# Cargador_RasPi3HAT_CamSlot_v1_1.net
KiCad netlist of a schematic drawn in EAGLE
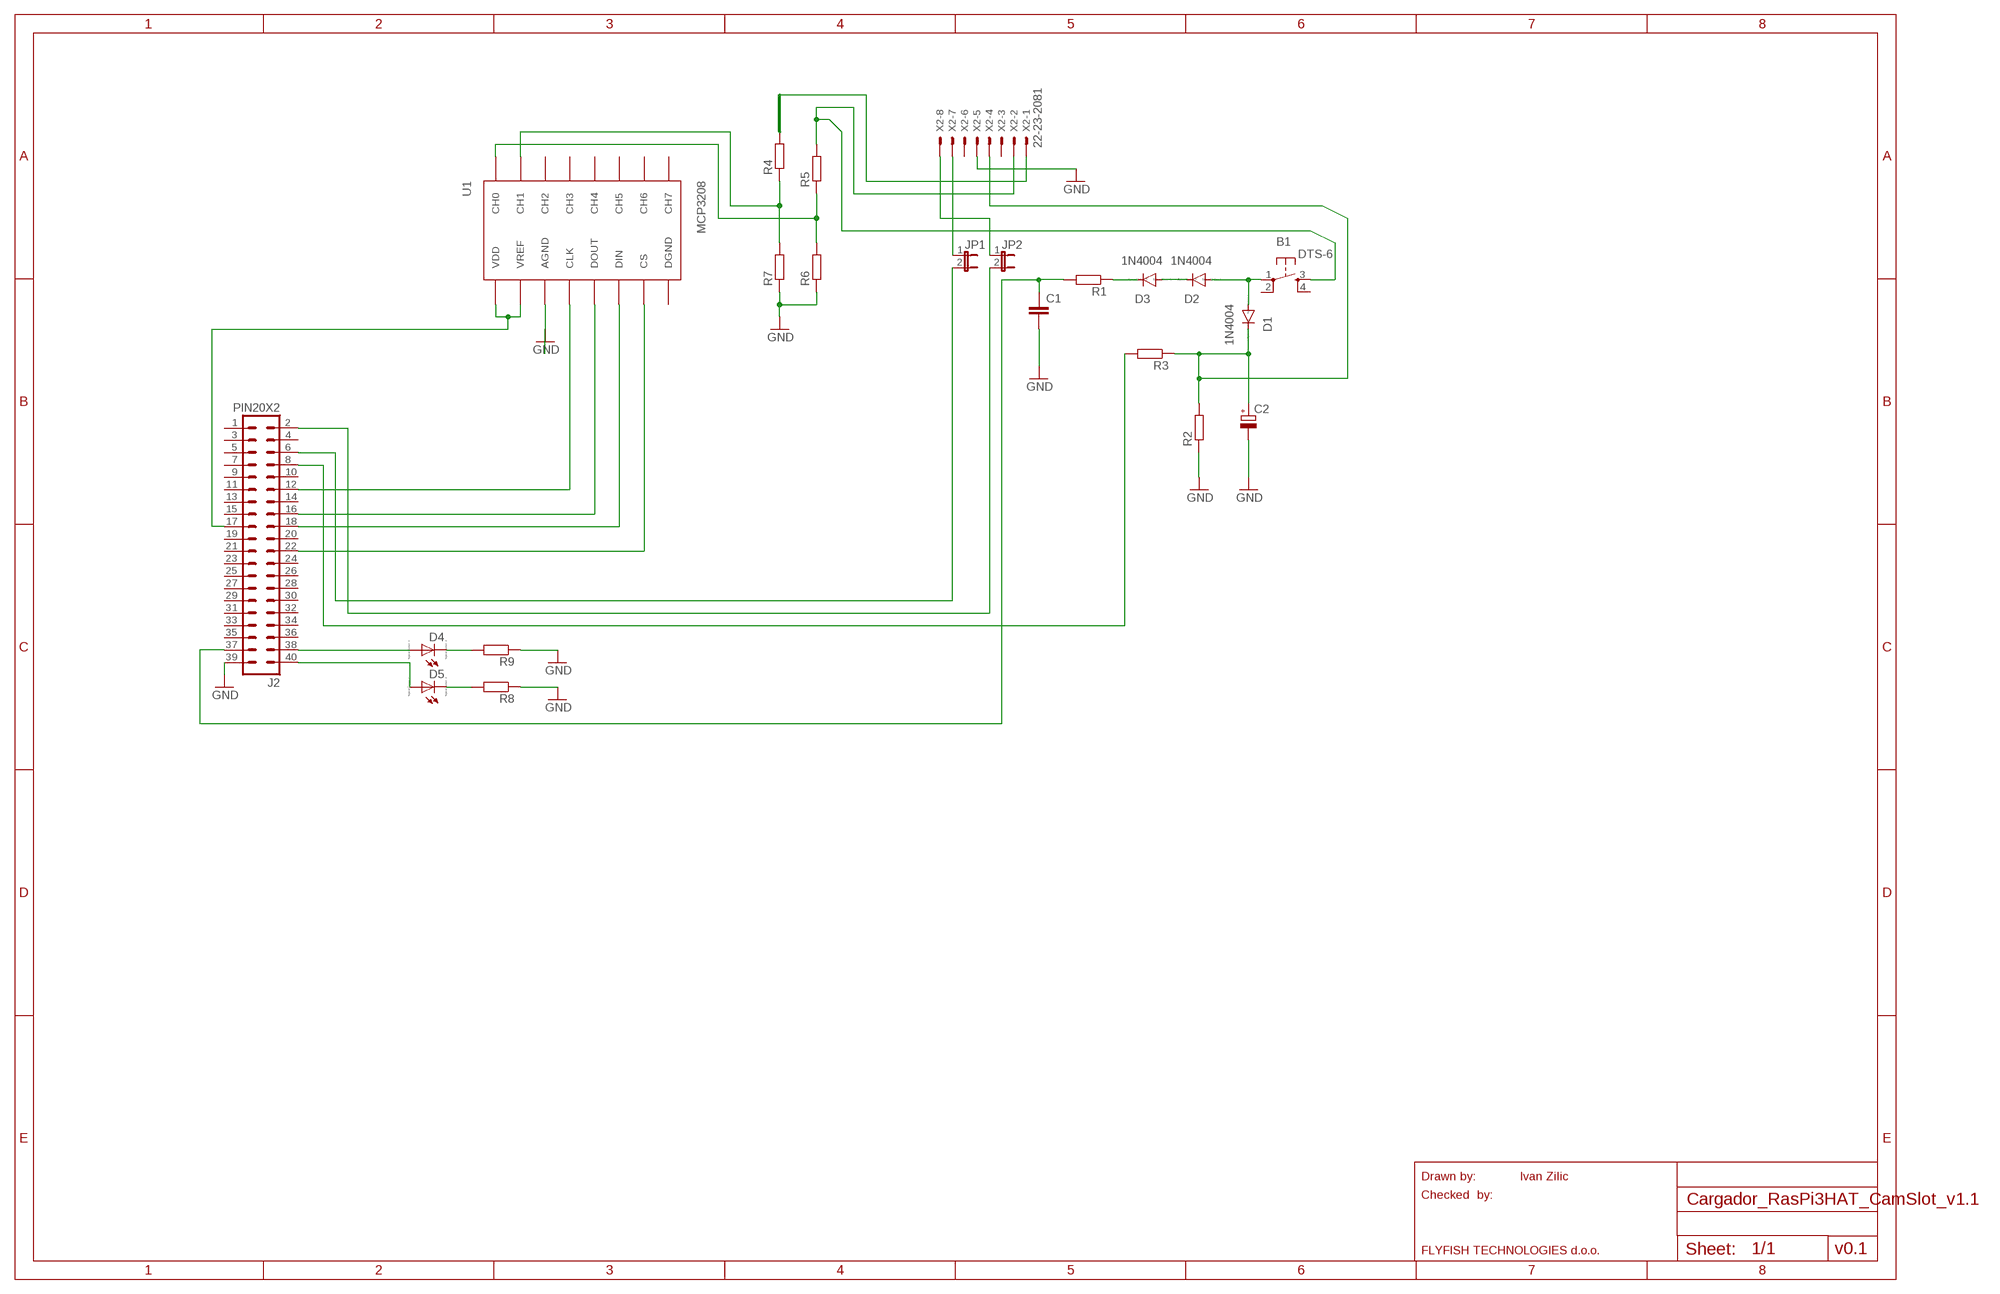
[diagram p0: schematic, sheet 1]

(export (version "E")
  (design (tool "Eeschema 10.0.6"))
  (components
    (comp (ref "B1")
      (value "DTS-6")
      (footprint "eagle-import:DTS-6")
      (libsource (lib "eagle-import") (part "DTS-6"))
    )
    (comp (ref "C1")
      (value "C2.5/2")
      (footprint "eagle-import:C2.5-2")
      (libsource (lib "eagle-import") (part "C2.5/2"))
    )
    (comp (ref "C2")
      (value "CPOL-EUE5-4")
      (footprint "eagle-import:E5-4")
      (libsource (lib "eagle-import") (part "CPOL-EUE5-4"))
    )
    (comp (ref "D1")
      (value "1N4004")
      (footprint "eagle-import:DO41-10")
      (libsource (lib "eagle-import") (part "1N4004"))
    )
    (comp (ref "D2")
      (value "1N4004")
      (footprint "eagle-import:DO41-10")
      (libsource (lib "eagle-import") (part "1N4004"))
    )
    (comp (ref "D3")
      (value "1N4004")
      (footprint "eagle-import:DO41-10")
      (libsource (lib "eagle-import") (part "1N4004"))
    )
    (comp (ref "D4")
      (value "LED_ELD260")
      (footprint "eagle-import:LED_LD260")
      (libsource (lib "eagle-import") (part "LED_ELD260"))
    )
    (comp (ref "D5")
      (value "LED_ELD260")
      (footprint "eagle-import:LED_LD260")
      (libsource (lib "eagle-import") (part "LED_ELD260"))
    )
    (comp (ref "J2")
      (value "PIN20X2")
      (footprint "eagle-import:PIN_20X2")
      (libsource (lib "eagle-import") (part "PIN20X2"))
    )
    (comp (ref "JP1")
      (value "JP1E")
      (footprint "eagle-import:JP1")
      (libsource (lib "eagle-import") (part "JP1E"))
    )
    (comp (ref "JP2")
      (value "JP1E")
      (footprint "eagle-import:JP1")
      (libsource (lib "eagle-import") (part "JP1E"))
    )
    (comp (ref "R1")
      (value "R-EU_0207/10")
      (footprint "eagle-import:0207_10")
      (libsource (lib "eagle-import") (part "R-EU_0207/10"))
    )
    (comp (ref "R2")
      (value "R-EU_0207/10")
      (footprint "eagle-import:0207_10")
      (libsource (lib "eagle-import") (part "R-EU_0207/10"))
    )
    (comp (ref "R3")
      (value "R-EU_0207/10")
      (footprint "eagle-import:0207_10")
      (libsource (lib "eagle-import") (part "R-EU_0207/10"))
    )
    (comp (ref "R4")
      (value "R-EU_0207/10")
      (footprint "eagle-import:0207_10")
      (libsource (lib "eagle-import") (part "R-EU_0207/10"))
    )
    (comp (ref "R5")
      (value "R-EU_0207/10")
      (footprint "eagle-import:0207_10")
      (libsource (lib "eagle-import") (part "R-EU_0207/10"))
    )
    (comp (ref "R6")
      (value "R-EU_0207/10")
      (footprint "eagle-import:0207_10")
      (libsource (lib "eagle-import") (part "R-EU_0207/10"))
    )
    (comp (ref "R7")
      (value "R-EU_0207/10")
      (footprint "eagle-import:0207_10")
      (libsource (lib "eagle-import") (part "R-EU_0207/10"))
    )
    (comp (ref "R8")
      (value "R-EU_0207/10")
      (footprint "eagle-import:0207_10")
      (libsource (lib "eagle-import") (part "R-EU_0207/10"))
    )
    (comp (ref "R9")
      (value "R-EU_0207/10")
      (footprint "eagle-import:0207_10")
      (libsource (lib "eagle-import") (part "R-EU_0207/10"))
    )
    (comp (ref "U1")
      (value "MCP3208")
      (footprint "eagle-import:DIL16")
      (libsource (lib "eagle-import") (part "MCP3208"))
    )
    (comp (ref "X2")
      (value "22-23-2081")
      (footprint "eagle-import:22-23-2081")
      (fields (field (name "MF") "MOLEX"))
      (libsource (lib "eagle-import") (part "22-23-2081"))
    )
  )
  (nets
    (net (code "1") (name "/DGND") (class "Default")
      (node (ref "U1") (pin "DGND") (pinfunction "DGND_DGND") (pintype "power_in"))
    )
    (net (code "2") (name "GND") (class "Default")
      (node (ref "C1") (pin "2") (pinfunction "2_2") (pintype "passive"))
      (node (ref "C2") (pin "-") (pinfunction "-_-") (pintype "passive"))
      (node (ref "J2") (pin "39") (pinfunction "39_39") (pintype "passive"))
      (node (ref "R2") (pin "1") (pinfunction "1_1") (pintype "passive"))
      (node (ref "R6") (pin "1") (pinfunction "1_1") (pintype "passive"))
      (node (ref "R7") (pin "1") (pinfunction "1_1") (pintype "passive"))
      (node (ref "R8") (pin "1") (pinfunction "1_1") (pintype "passive"))
      (node (ref "R9") (pin "1") (pinfunction "1_1") (pintype "passive"))
      (node (ref "U1") (pin "AGND") (pinfunction "AGND_AGND") (pintype "power_in"))
      (node (ref "X2") (pin "5") (pinfunction "S_5") (pintype "passive"))
    )
    (net (code "3") (name "Net-(B1-Pad1)") (class "Default")
      (node (ref "B1") (pin "1") (pinfunction "1_1") (pintype "passive"))
      (node (ref "D1") (pin "A") (pinfunction "A_A") (pintype "passive"))
      (node (ref "D2") (pin "A") (pinfunction "A_A") (pintype "passive"))
    )
    (net (code "4") (name "Net-(C1-Pad1)") (class "Default")
      (node (ref "C1") (pin "1") (pinfunction "1_1") (pintype "passive"))
      (node (ref "J2") (pin "37") (pinfunction "37_37") (pintype "passive"))
      (node (ref "R1") (pin "2") (pinfunction "2_2") (pintype "passive"))
    )
    (net (code "5") (name "Net-(D2-PadC)") (class "Default")
      (node (ref "D2") (pin "C") (pinfunction "C_C") (pintype "passive"))
      (node (ref "D3") (pin "A") (pinfunction "A_A") (pintype "passive"))
    )
    (net (code "6") (name "Net-(D3-PadC)") (class "Default")
      (node (ref "D3") (pin "C") (pinfunction "C_C") (pintype "passive"))
      (node (ref "R1") (pin "1") (pinfunction "1_1") (pintype "passive"))
    )
    (net (code "7") (name "Net-(D4-C)") (class "Default")
      (node (ref "D4") (pin "K") (pinfunction "C_K") (pintype "passive"))
      (node (ref "R9") (pin "2") (pinfunction "2_2") (pintype "passive"))
    )
    (net (code "8") (name "Net-(D4-PadA)") (class "Default")
      (node (ref "D4") (pin "A") (pinfunction "A_A") (pintype "passive"))
      (node (ref "J2") (pin "38") (pinfunction "38_38") (pintype "passive"))
    )
    (net (code "9") (name "Net-(D5-C)") (class "Default")
      (node (ref "D5") (pin "K") (pinfunction "C_K") (pintype "passive"))
      (node (ref "R8") (pin "2") (pinfunction "2_2") (pintype "passive"))
    )
    (net (code "10") (name "Net-(D5-PadA)") (class "Default")
      (node (ref "D5") (pin "A") (pinfunction "A_A") (pintype "passive"))
      (node (ref "J2") (pin "40") (pinfunction "40_40") (pintype "passive"))
    )
    (net (code "11") (name "Net-(J2-Pad2)") (class "Default")
      (node (ref "J2") (pin "2") (pinfunction "2_2") (pintype "passive"))
      (node (ref "JP2") (pin "2") (pinfunction "2_2") (pintype "passive"))
    )
    (net (code "12") (name "Net-(J2-Pad6)") (class "Default")
      (node (ref "J2") (pin "6") (pinfunction "6_6") (pintype "passive"))
      (node (ref "JP1") (pin "2") (pinfunction "2_2") (pintype "passive"))
    )
    (net (code "13") (name "Net-(J2-Pad8)") (class "Default")
      (node (ref "J2") (pin "8") (pinfunction "8_8") (pintype "passive"))
      (node (ref "R3") (pin "2") (pinfunction "2_2") (pintype "passive"))
    )
    (net (code "14") (name "Net-(J2-Pad12)") (class "Default")
      (node (ref "J2") (pin "12") (pinfunction "12_12") (pintype "passive"))
      (node (ref "U1") (pin "CLK") (pinfunction "CLK_CLK") (pintype "input"))
    )
    (net (code "15") (name "Net-(J2-Pad16)") (class "Default")
      (node (ref "J2") (pin "16") (pinfunction "16_16") (pintype "passive"))
      (node (ref "U1") (pin "DOUT") (pinfunction "DOUT_DOUT") (pintype "output"))
    )
    (net (code "16") (name "Net-(J2-Pad17)") (class "Default")
      (node (ref "J2") (pin "17") (pinfunction "17_17") (pintype "passive"))
      (node (ref "U1") (pin "VDD") (pinfunction "VDD_VDD") (pintype "power_in"))
      (node (ref "U1") (pin "VREF") (pinfunction "VREF_VREF") (pintype "input"))
    )
    (net (code "17") (name "Net-(J2-Pad18)") (class "Default")
      (node (ref "J2") (pin "18") (pinfunction "18_18") (pintype "passive"))
      (node (ref "U1") (pin "DIN") (pinfunction "DIN_DIN") (pintype "input"))
    )
    (net (code "18") (name "Net-(J2-Pad22)") (class "Default")
      (node (ref "J2") (pin "22") (pinfunction "22_22") (pintype "passive"))
      (node (ref "U1") (pin "CS") (pinfunction "CS_CS") (pintype "input"))
    )
    (net (code "19") (name "Net-(R4-Pad1)") (class "Default")
      (node (ref "R4") (pin "1") (pinfunction "1_1") (pintype "passive"))
      (node (ref "R7") (pin "2") (pinfunction "2_2") (pintype "passive"))
      (node (ref "U1") (pin "CH1") (pinfunction "CH1_CH1") (pintype "input"))
    )
    (net (code "20") (name "Net-(R5-Pad1)") (class "Default")
      (node (ref "R5") (pin "1") (pinfunction "1_1") (pintype "passive"))
      (node (ref "R6") (pin "2") (pinfunction "2_2") (pintype "passive"))
      (node (ref "U1") (pin "CH0") (pinfunction "CH0_CH0") (pintype "input"))
    )
    (net (code "21") (name "Net-(X2A-S)") (class "Default")
      (node (ref "R4") (pin "2") (pinfunction "2_2") (pintype "passive"))
      (node (ref "X2") (pin "1") (pinfunction "S_1") (pintype "passive"))
    )
    (net (code "22") (name "Net-(X2B-S)") (class "Default")
      (node (ref "B1") (pin "3") (pinfunction "3_3") (pintype "passive"))
      (node (ref "R5") (pin "2") (pinfunction "2_2") (pintype "passive"))
      (node (ref "X2") (pin "2") (pinfunction "S_2") (pintype "passive"))
    )
    (net (code "23") (name "Net-(X2D-S)") (class "Default")
      (node (ref "C2") (pin "+") (pinfunction "+_+") (pintype "passive"))
      (node (ref "D1") (pin "C") (pinfunction "C_C") (pintype "passive"))
      (node (ref "R2") (pin "2") (pinfunction "2_2") (pintype "passive"))
      (node (ref "R3") (pin "1") (pinfunction "1_1") (pintype "passive"))
      (node (ref "X2") (pin "4") (pinfunction "S_4") (pintype "passive"))
    )
    (net (code "24") (name "Net-(X2G-S)") (class "Default")
      (node (ref "JP1") (pin "1") (pinfunction "1_1") (pintype "passive"))
      (node (ref "X2") (pin "7") (pinfunction "S_7") (pintype "passive"))
    )
    (net (code "25") (name "Net-(X2H-S)") (class "Default")
      (node (ref "JP2") (pin "1") (pinfunction "1_1") (pintype "passive"))
      (node (ref "X2") (pin "8") (pinfunction "S_8") (pintype "passive"))
    )
    (net (code "26") (name "unconnected-(B1-Pad2)") (class "Default")
      (node (ref "B1") (pin "2") (pinfunction "2_2") (pintype "passive"))
    )
    (net (code "27") (name "unconnected-(B1-Pad4)") (class "Default")
      (node (ref "B1") (pin "4") (pinfunction "4_4") (pintype "passive"))
    )
    (net (code "28") (name "unconnected-(J2-Pad1)") (class "Default")
      (node (ref "J2") (pin "1") (pinfunction "1_1") (pintype "passive"))
    )
    (net (code "29") (name "unconnected-(J2-Pad3)") (class "Default")
      (node (ref "J2") (pin "3") (pinfunction "3_3") (pintype "passive"))
    )
    (net (code "30") (name "unconnected-(J2-Pad4)") (class "Default")
      (node (ref "J2") (pin "4") (pinfunction "4_4") (pintype "passive"))
    )
    (net (code "31") (name "unconnected-(J2-Pad5)") (class "Default")
      (node (ref "J2") (pin "5") (pinfunction "5_5") (pintype "passive"))
    )
    (net (code "32") (name "unconnected-(J2-Pad7)") (class "Default")
      (node (ref "J2") (pin "7") (pinfunction "7_7") (pintype "passive"))
    )
    (net (code "33") (name "unconnected-(J2-Pad9)") (class "Default")
      (node (ref "J2") (pin "9") (pinfunction "9_9") (pintype "passive"))
    )
    (net (code "34") (name "unconnected-(J2-Pad10)") (class "Default")
      (node (ref "J2") (pin "10") (pinfunction "10_10") (pintype "passive"))
    )
    (net (code "35") (name "unconnected-(J2-Pad11)") (class "Default")
      (node (ref "J2") (pin "11") (pinfunction "11_11") (pintype "passive"))
    )
    (net (code "36") (name "unconnected-(J2-Pad13)") (class "Default")
      (node (ref "J2") (pin "13") (pinfunction "13_13") (pintype "passive"))
    )
    (net (code "37") (name "unconnected-(J2-Pad14)") (class "Default")
      (node (ref "J2") (pin "14") (pinfunction "14_14") (pintype "passive"))
    )
    (net (code "38") (name "unconnected-(J2-Pad15)") (class "Default")
      (node (ref "J2") (pin "15") (pinfunction "15_15") (pintype "passive"))
    )
    (net (code "39") (name "unconnected-(J2-Pad19)") (class "Default")
      (node (ref "J2") (pin "19") (pinfunction "19_19") (pintype "passive"))
    )
    (net (code "40") (name "unconnected-(J2-Pad20)") (class "Default")
      (node (ref "J2") (pin "20") (pinfunction "20_20") (pintype "passive"))
    )
    (net (code "41") (name "unconnected-(J2-Pad21)") (class "Default")
      (node (ref "J2") (pin "21") (pinfunction "21_21") (pintype "passive"))
    )
    (net (code "42") (name "unconnected-(J2-Pad23)") (class "Default")
      (node (ref "J2") (pin "23") (pinfunction "23_23") (pintype "passive"))
    )
    (net (code "43") (name "unconnected-(J2-Pad24)") (class "Default")
      (node (ref "J2") (pin "24") (pinfunction "24_24") (pintype "passive"))
    )
    (net (code "44") (name "unconnected-(J2-Pad25)") (class "Default")
      (node (ref "J2") (pin "25") (pinfunction "25_25") (pintype "passive"))
    )
    (net (code "45") (name "unconnected-(J2-Pad26)") (class "Default")
      (node (ref "J2") (pin "26") (pinfunction "26_26") (pintype "passive"))
    )
    (net (code "46") (name "unconnected-(J2-Pad27)") (class "Default")
      (node (ref "J2") (pin "27") (pinfunction "27_27") (pintype "passive"))
    )
    (net (code "47") (name "unconnected-(J2-Pad28)") (class "Default")
      (node (ref "J2") (pin "28") (pinfunction "28_28") (pintype "passive"))
    )
    (net (code "48") (name "unconnected-(J2-Pad29)") (class "Default")
      (node (ref "J2") (pin "29") (pinfunction "29_29") (pintype "passive"))
    )
    (net (code "49") (name "unconnected-(J2-Pad30)") (class "Default")
      (node (ref "J2") (pin "30") (pinfunction "30_30") (pintype "passive"))
    )
    (net (code "50") (name "unconnected-(J2-Pad31)") (class "Default")
      (node (ref "J2") (pin "31") (pinfunction "31_31") (pintype "passive"))
    )
    (net (code "51") (name "unconnected-(J2-Pad32)") (class "Default")
      (node (ref "J2") (pin "32") (pinfunction "32_32") (pintype "passive"))
    )
    (net (code "52") (name "unconnected-(J2-Pad33)") (class "Default")
      (node (ref "J2") (pin "33") (pinfunction "33_33") (pintype "passive"))
    )
    (net (code "53") (name "unconnected-(J2-Pad34)") (class "Default")
      (node (ref "J2") (pin "34") (pinfunction "34_34") (pintype "passive"))
    )
    (net (code "54") (name "unconnected-(J2-Pad35)") (class "Default")
      (node (ref "J2") (pin "35") (pinfunction "35_35") (pintype "passive"))
    )
    (net (code "55") (name "unconnected-(J2-Pad36)") (class "Default")
      (node (ref "J2") (pin "36") (pinfunction "36_36") (pintype "passive"))
    )
    (net (code "56") (name "unconnected-(U1-PadCH2)") (class "Default")
      (node (ref "U1") (pin "CH2") (pinfunction "CH2_CH2") (pintype "input"))
    )
    (net (code "57") (name "unconnected-(U1-PadCH3)") (class "Default")
      (node (ref "U1") (pin "CH3") (pinfunction "CH3_CH3") (pintype "input"))
    )
    (net (code "58") (name "unconnected-(U1-PadCH4)") (class "Default")
      (node (ref "U1") (pin "CH4") (pinfunction "CH4_CH4") (pintype "input"))
    )
    (net (code "59") (name "unconnected-(U1-PadCH5)") (class "Default")
      (node (ref "U1") (pin "CH5") (pinfunction "CH5_CH5") (pintype "input"))
    )
    (net (code "60") (name "unconnected-(U1-PadCH6)") (class "Default")
      (node (ref "U1") (pin "CH6") (pinfunction "CH6_CH6") (pintype "input"))
    )
    (net (code "61") (name "unconnected-(U1-PadCH7)") (class "Default")
      (node (ref "U1") (pin "CH7") (pinfunction "CH7_CH7") (pintype "input"))
    )
    (net (code "62") (name "unconnected-(X2C-S-Pad3)") (class "Default")
      (node (ref "X2") (pin "3") (pinfunction "S_3") (pintype "passive"))
    )
    (net (code "63") (name "unconnected-(X2F-S-Pad6)") (class "Default")
      (node (ref "X2") (pin "6") (pinfunction "S_6") (pintype "passive"))
    )
  )
)
